# OSO-MISC-21-004_Sensor_Watch_Testpoints.net
KiCad netlist of a schematic drawn in EAGLE
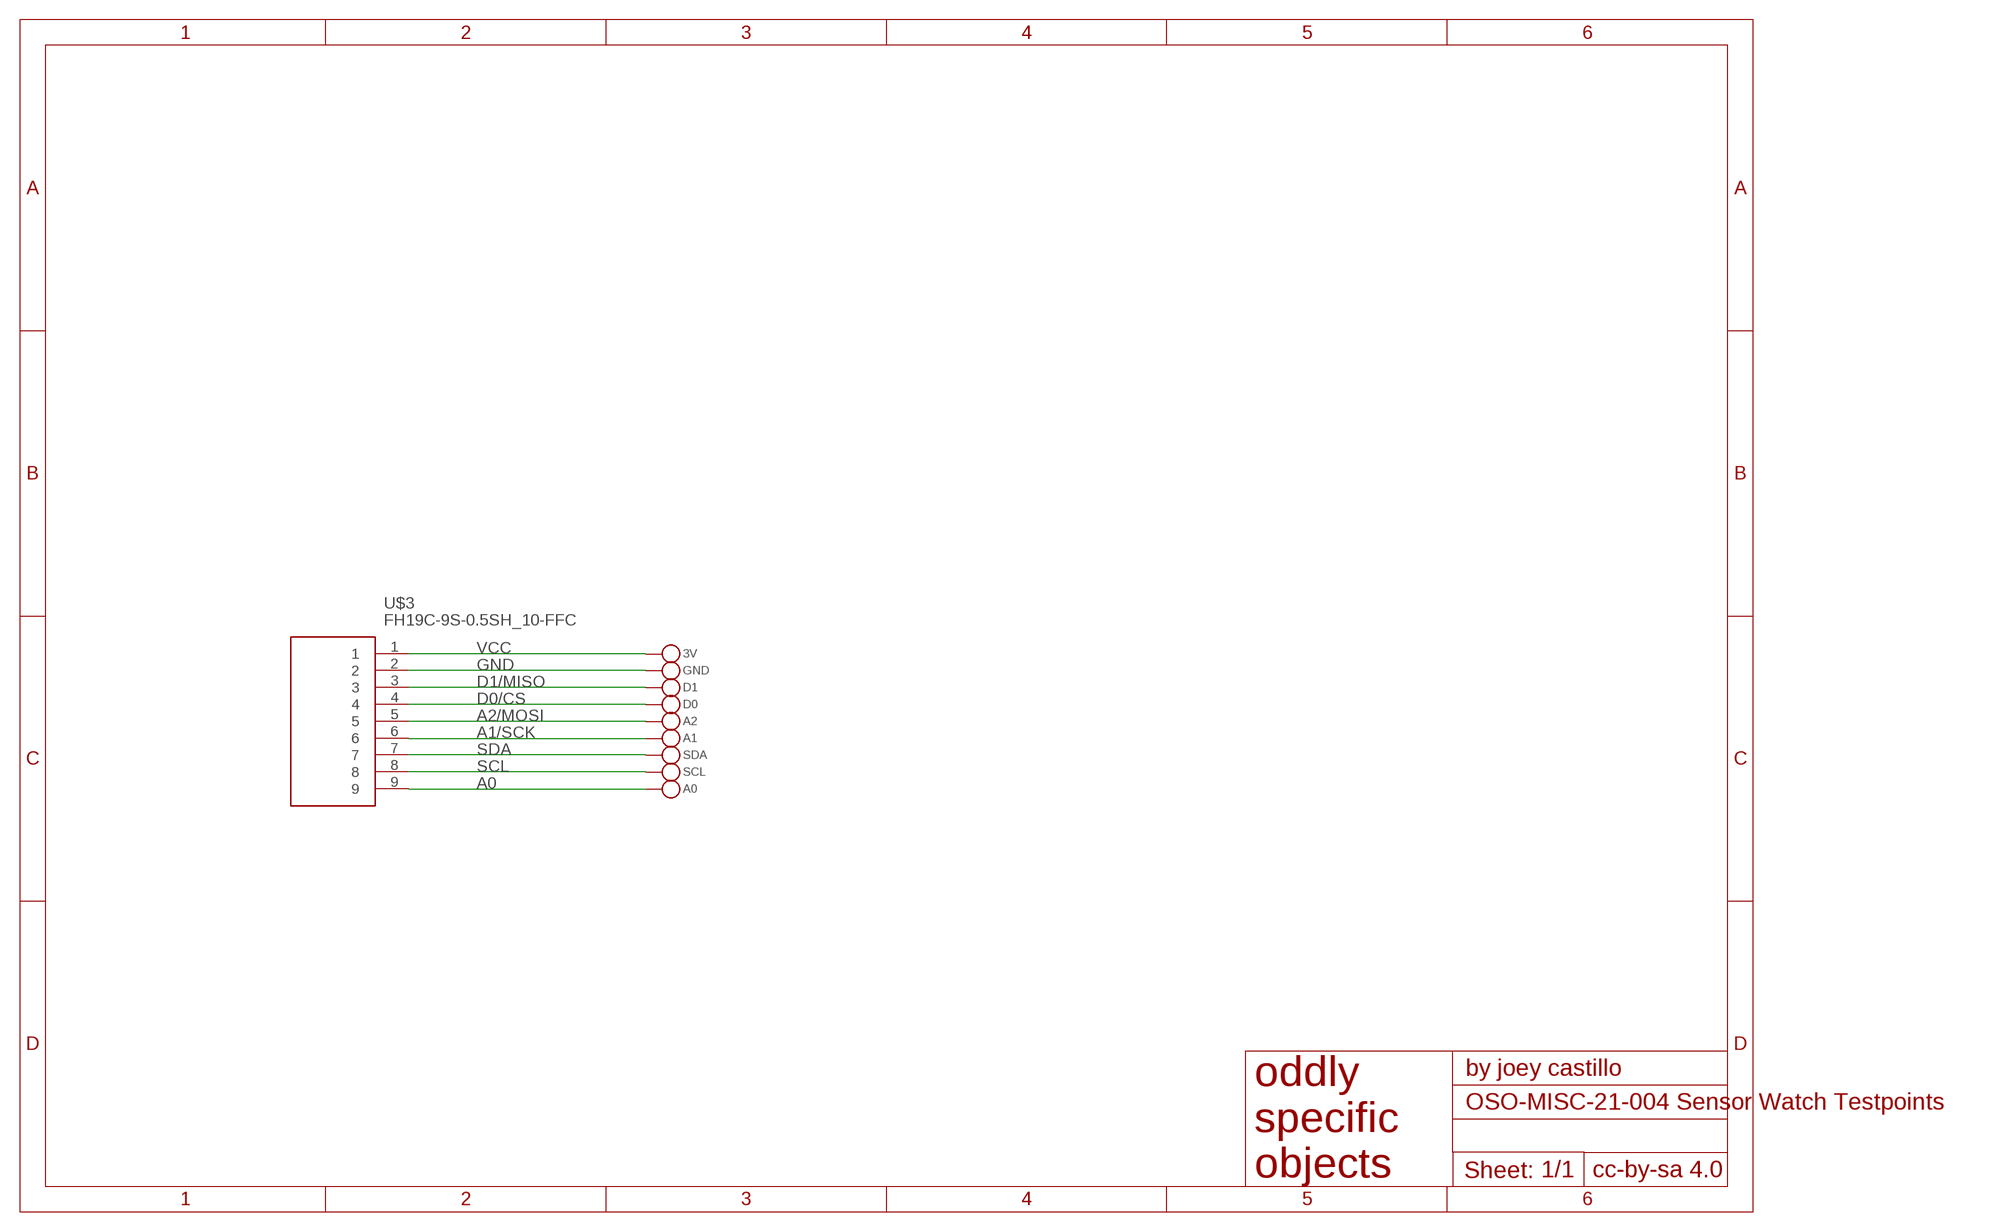
[diagram p0: schematic, sheet 1]

(export (version "E")
  (design (tool "Eeschema 10.0.6"))
  (components
    (comp (ref "3V")
      (value "MICROBUILDER_TESTPOINT1.5X2.0MM_NOCREAM")
      (footprint "eagle-import:MICROBUILDER_PAD-1.5X2.0")
      (libsource (lib "eagle-import") (part "MICROBUILDER_TESTPOINT1.5X2.0MM_NOCREAM"))
    )
    (comp (ref "A0")
      (value "MICROBUILDER_TESTPOINT1.5X2.0MM_NOCREAM")
      (footprint "eagle-import:MICROBUILDER_PAD-1.5X2.0")
      (libsource (lib "eagle-import") (part "MICROBUILDER_TESTPOINT1.5X2.0MM_NOCREAM"))
    )
    (comp (ref "A1")
      (value "MICROBUILDER_TESTPOINT1.5X2.0MM_NOCREAM")
      (footprint "eagle-import:MICROBUILDER_PAD-1.5X2.0")
      (libsource (lib "eagle-import") (part "MICROBUILDER_TESTPOINT1.5X2.0MM_NOCREAM"))
    )
    (comp (ref "A2")
      (value "MICROBUILDER_TESTPOINT1.5X2.0MM_NOCREAM")
      (footprint "eagle-import:MICROBUILDER_PAD-1.5X2.0")
      (libsource (lib "eagle-import") (part "MICROBUILDER_TESTPOINT1.5X2.0MM_NOCREAM"))
    )
    (comp (ref "D0")
      (value "MICROBUILDER_TESTPOINT1.5X2.0MM_NOCREAM")
      (footprint "eagle-import:MICROBUILDER_PAD-1.5X2.0")
      (libsource (lib "eagle-import") (part "MICROBUILDER_TESTPOINT1.5X2.0MM_NOCREAM"))
    )
    (comp (ref "D1")
      (value "MICROBUILDER_TESTPOINT1.5X2.0MM_NOCREAM")
      (footprint "eagle-import:MICROBUILDER_PAD-1.5X2.0")
      (libsource (lib "eagle-import") (part "MICROBUILDER_TESTPOINT1.5X2.0MM_NOCREAM"))
    )
    (comp (ref "GND")
      (value "MICROBUILDER_TESTPOINT1.5X2.0MM_NOCREAM")
      (footprint "eagle-import:MICROBUILDER_PAD-1.5X2.0")
      (libsource (lib "eagle-import") (part "MICROBUILDER_TESTPOINT1.5X2.0MM_NOCREAM"))
    )
    (comp (ref "SCL")
      (value "MICROBUILDER_TESTPOINT1.5X2.0MM_NOCREAM")
      (footprint "eagle-import:MICROBUILDER_PAD-1.5X2.0")
      (libsource (lib "eagle-import") (part "MICROBUILDER_TESTPOINT1.5X2.0MM_NOCREAM"))
    )
    (comp (ref "SDA")
      (value "MICROBUILDER_TESTPOINT1.5X2.0MM_NOCREAM")
      (footprint "eagle-import:MICROBUILDER_PAD-1.5X2.0")
      (libsource (lib "eagle-import") (part "MICROBUILDER_TESTPOINT1.5X2.0MM_NOCREAM"))
    )
    (comp (ref "U$3")
      (value "FH19C-9S-0.5SH_10-FFC")
      (footprint "eagle-import:FH19C9S05SH10-FFC")
      (libsource (lib "eagle-import") (part "FH19C-9S-0.5SH_10-FFC"))
    )
  )
  (nets
    (net (code "1") (name "/A0") (class "Default")
      (node (ref "A0") (pin "P$1") (pinfunction "P$1_P$1") (pintype "bidirectional"))
      (node (ref "U$3") (pin "9") (pinfunction "9_9") (pintype "bidirectional"))
    )
    (net (code "2") (name "/A1{slash}SCK") (class "Default")
      (node (ref "A1") (pin "P$1") (pinfunction "P$1_P$1") (pintype "bidirectional"))
      (node (ref "U$3") (pin "6") (pinfunction "6_6") (pintype "bidirectional"))
    )
    (net (code "3") (name "/A2{slash}MOSI") (class "Default")
      (node (ref "A2") (pin "P$1") (pinfunction "P$1_P$1") (pintype "bidirectional"))
      (node (ref "U$3") (pin "5") (pinfunction "5_5") (pintype "bidirectional"))
    )
    (net (code "4") (name "/D0{slash}CS") (class "Default")
      (node (ref "D0") (pin "P$1") (pinfunction "P$1_P$1") (pintype "bidirectional"))
      (node (ref "U$3") (pin "4") (pinfunction "4_4") (pintype "bidirectional"))
    )
    (net (code "5") (name "/D1{slash}MISO") (class "Default")
      (node (ref "D1") (pin "P$1") (pinfunction "P$1_P$1") (pintype "bidirectional"))
      (node (ref "U$3") (pin "3") (pinfunction "3_3") (pintype "bidirectional"))
    )
    (net (code "6") (name "/GND") (class "Default")
      (node (ref "GND") (pin "P$1") (pinfunction "P$1_P$1") (pintype "bidirectional"))
      (node (ref "U$3") (pin "2") (pinfunction "2_2") (pintype "bidirectional"))
    )
    (net (code "7") (name "/SCL") (class "Default")
      (node (ref "SCL") (pin "P$1") (pinfunction "P$1_P$1") (pintype "bidirectional"))
      (node (ref "U$3") (pin "8") (pinfunction "8_8") (pintype "bidirectional"))
    )
    (net (code "8") (name "/SDA") (class "Default")
      (node (ref "SDA") (pin "P$1") (pinfunction "P$1_P$1") (pintype "bidirectional"))
      (node (ref "U$3") (pin "7") (pinfunction "7_7") (pintype "bidirectional"))
    )
    (net (code "9") (name "/VCC") (class "Default")
      (node (ref "3V") (pin "P$1") (pinfunction "P$1_P$1") (pintype "bidirectional"))
      (node (ref "U$3") (pin "1") (pinfunction "1_1") (pintype "bidirectional"))
    )
  )
)
